# motordriver-v3_1_A3931.net
KiCad netlist of a schematic drawn in Altium Designer
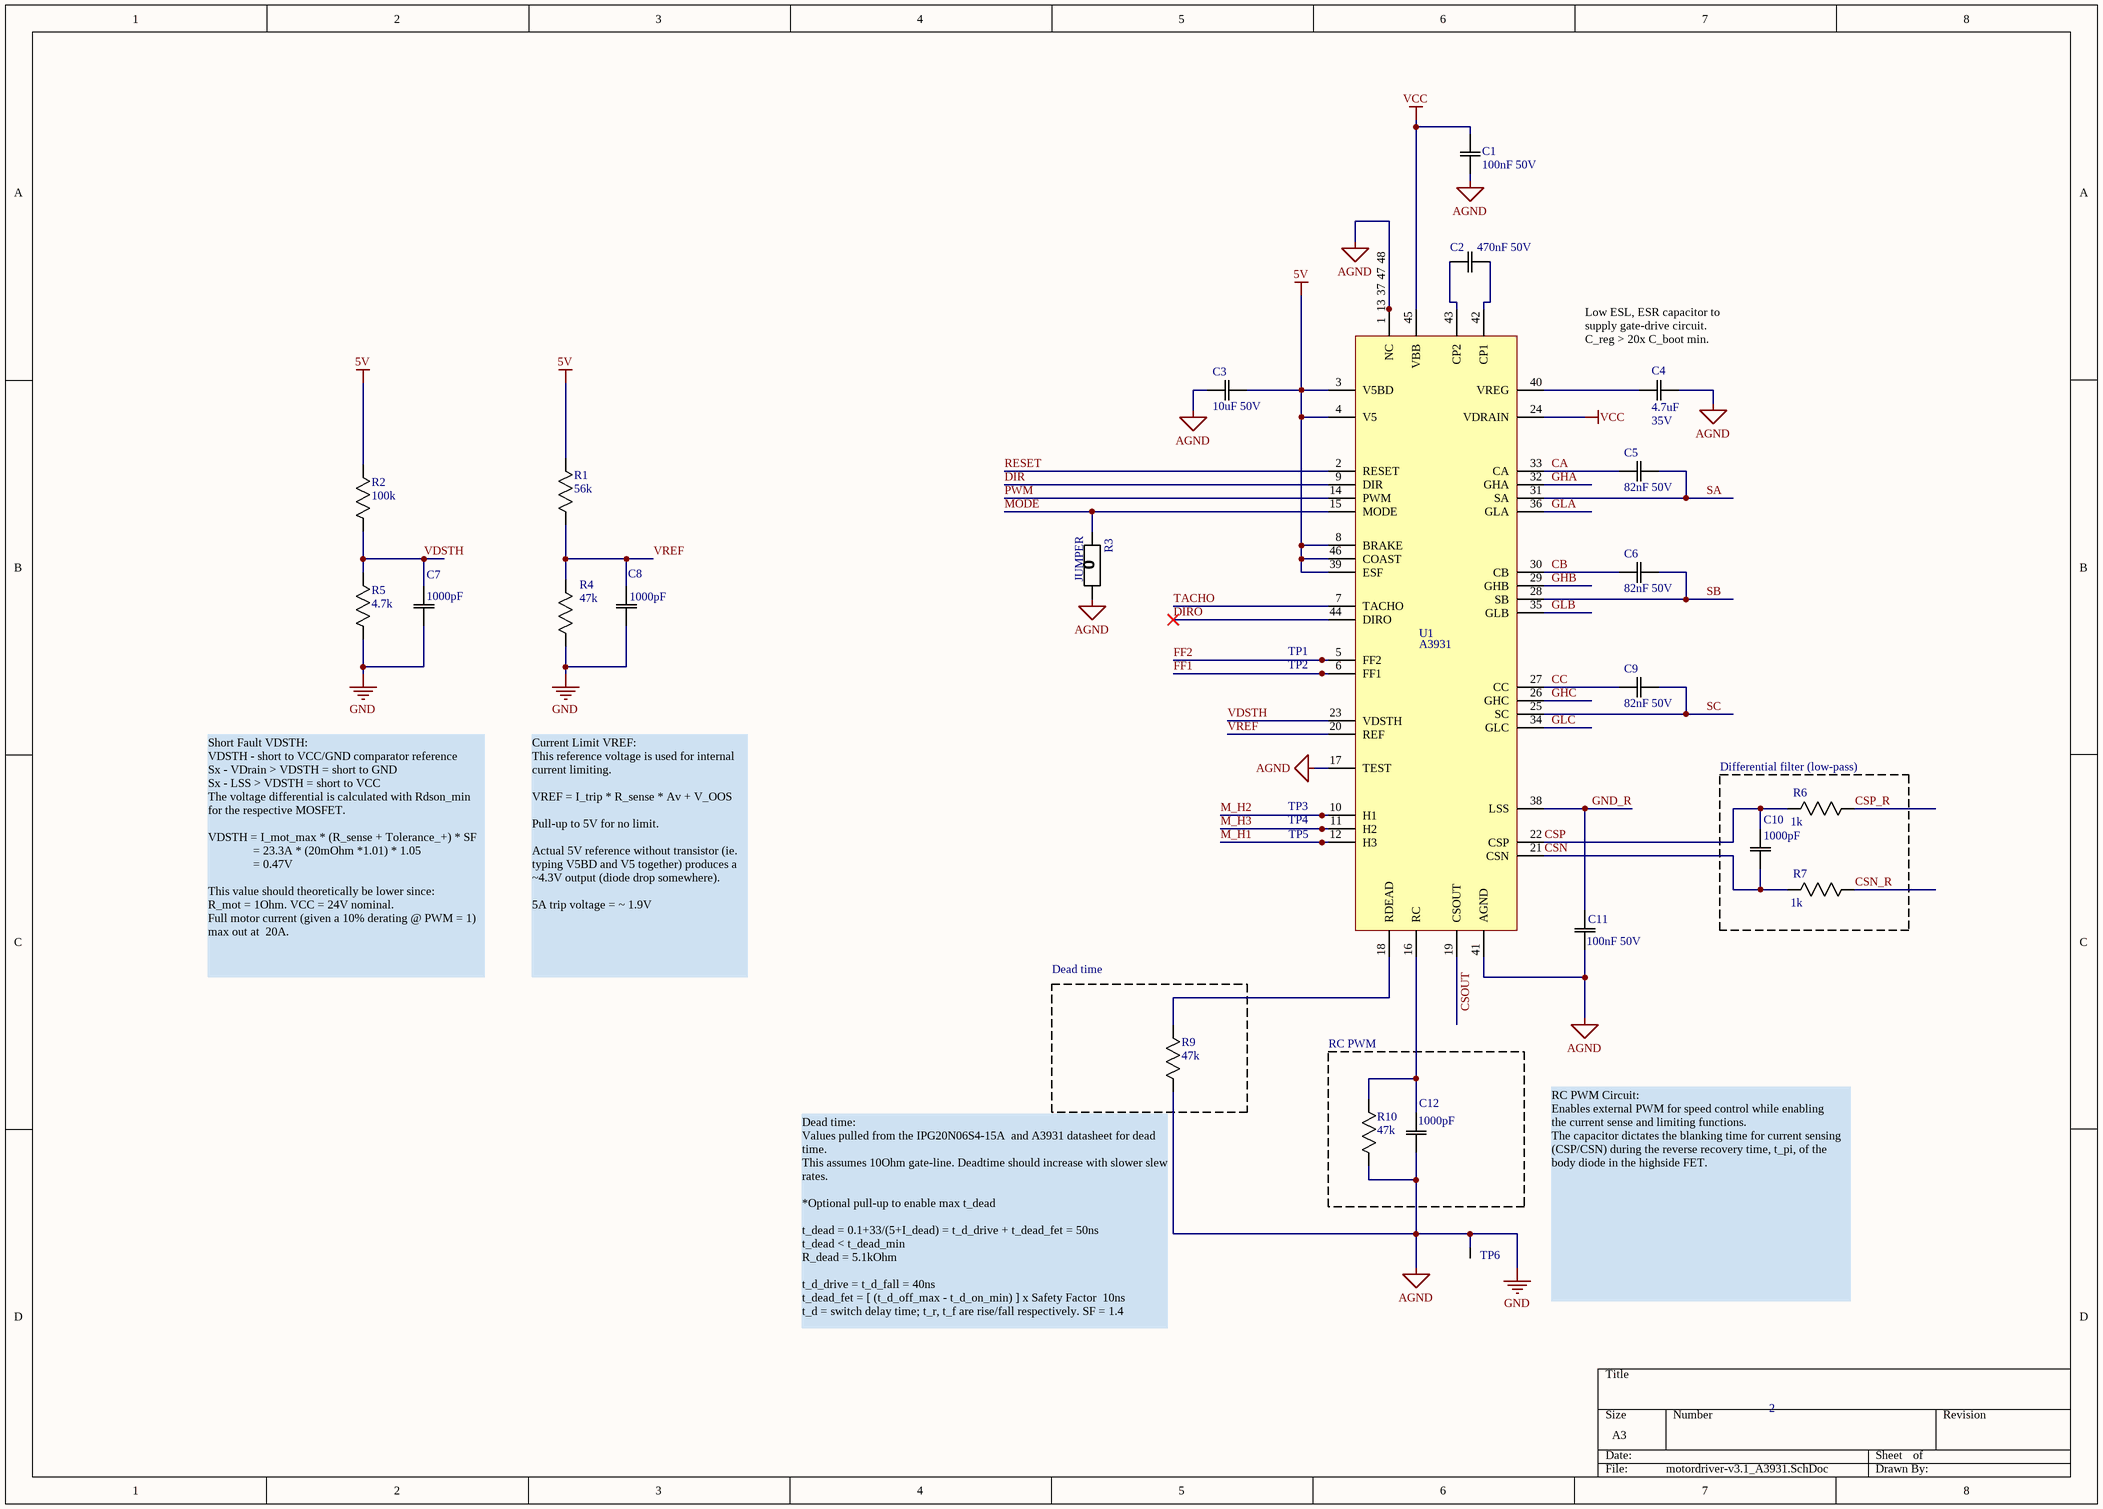
[diagram p0: motordriver-v3.1_A3931.SchDoc]

(export (version "E")
  (design (tool "Eeschema 10.0.6"))
  (components
    (comp (ref "C1")
      (value "100nF 50V")
      (footprint "0603")
      (description "CAP CER 0.1UF 50V X7R 0805")
      (fields (field (name "TOLERANCE") "10%"))
      (libsource (lib "AltiumLibraries") (part "CAP 100nF 50V"))
    )
    (comp (ref "C2")
      (value "470nF 50V")
      (footprint "0603")
      (description "CAP CER 0.1UF 50V X7R 0805")
      (fields (field (name "TOLERANCE") "10%"))
      (libsource (lib "AltiumLibraries") (part "CAP 470nF 50V"))
    )
    (comp (ref "C3")
      (value "10uF 50V")
      (footprint "0805")
      (description "CAP CER 10UF 50V X7R")
      (fields (field (name "TOLERANCE") "10%"))
      (libsource (lib "AltiumLibraries") (part "CAP 10uF 50V"))
    )
    (comp (ref "C4")
      (value "4.7uF")
      (footprint "0603")
      (description "CAP CER 4.7UF 35V X7R 0603/0805")
      (fields (field (name "TOLERANCE") "10%") (field (name "RATING") "35V"))
      (libsource (lib "AltiumLibraries") (part "CAP 4.7uF 35V"))
    )
    (comp (ref "C5")
      (value "82nF 50V")
      (footprint "0603")
      (description "CAP CER 0.082UF 50V X7R 0805")
      (fields (field (name "TOLERANCE") "5%"))
      (libsource (lib "AltiumLibraries") (part "CAP 82nF 50V"))
    )
    (comp (ref "C6")
      (value "82nF 50V")
      (footprint "0603")
      (description "CAP CER 0.082UF 50V X7R 0805")
      (fields (field (name "TOLERANCE") "5%"))
      (libsource (lib "AltiumLibraries") (part "CAP 82nF 50V"))
    )
    (comp (ref "C7")
      (value "1000pF")
      (footprint "0603")
      (description "CAP CER 1000PF 50V X7R 0603/0805")
      (fields (field (name "TOLERANCE") "10%"))
      (libsource (lib "AltiumLibraries") (part "CAP 1000pF 50V"))
    )
    (comp (ref "C8")
      (value "1000pF")
      (footprint "0603")
      (description "CAP CER 1000PF 50V X7R 0603/0805")
      (fields (field (name "TOLERANCE") "10%"))
      (libsource (lib "AltiumLibraries") (part "CAP 1000pF 50V"))
    )
    (comp (ref "C9")
      (value "82nF 50V")
      (footprint "0603")
      (description "CAP CER 0.082UF 50V X7R 0805")
      (fields (field (name "TOLERANCE") "5%"))
      (libsource (lib "AltiumLibraries") (part "CAP 82nF 50V"))
    )
    (comp (ref "C10")
      (value "1000pF")
      (footprint "0603")
      (description "CAP CER 1000PF 50V X7R 0603/0805")
      (fields (field (name "TOLERANCE") "10%"))
      (libsource (lib "AltiumLibraries") (part "CAP 1000pF 50V"))
    )
    (comp (ref "C11")
      (value "100nF 50V")
      (footprint "0603")
      (description "CAP CER 0.1UF 50V X7R 0805")
      (fields (field (name "TOLERANCE") "10%"))
      (libsource (lib "AltiumLibraries") (part "CAP 100nF 50V"))
    )
    (comp (ref "C12")
      (value "1000pF")
      (footprint "0603")
      (description "CAP CER 1000PF 50V X7R 0603/0805")
      (fields (field (name "TOLERANCE") "10%"))
      (libsource (lib "AltiumLibraries") (part "CAP 1000pF 50V"))
    )
    (comp (ref "R1")
      (value "56k")
      (footprint "0603")
      (description "RES SMD 100K OHM 1% 1/8W 0805")
      (fields (field (name "TOLERANCE") "1%"))
      (libsource (lib "") (part "RES 100k 1/8W - 1%_1"))
    )
    (comp (ref "R2")
      (value "100k")
      (footprint "0603")
      (description "RES SMD 100K OHM 1% 1/8W 0805")
      (fields (field (name "TOLERANCE") "1%"))
      (libsource (lib "AltiumLibraries") (part "RES 100k 1/8W - 1%"))
    )
    (comp (ref "R3")
      (value "JUMPER")
      (footprint "0603")
      (description "RES SMD 0 OHM JUMPER GENERIC 0805")
      (libsource (lib "AltiumLibraries") (part "RES 0 JUMPER"))
    )
    (comp (ref "R4")
      (value "47k")
      (footprint "0603")
      (description "RES SMD 47K OHM 1% 1/8W 0805")
      (fields (field (name "TOLERANCE") "1%"))
      (libsource (lib "") (part "RES 47k 1/8W - 1%_1"))
    )
    (comp (ref "R5")
      (value "4.7k")
      (footprint "0603")
      (description "RES SMD 4.7k OHM 1% 1/8W 0805")
      (fields (field (name "TOLERANCE") "1%"))
      (libsource (lib "AltiumLibraries") (part "RES 4.7k 1/8W - 1%"))
    )
    (comp (ref "R6")
      (value "1k")
      (footprint "0603")
      (description "RES SMD 1K OHM 5% 1/8W 0805")
      (fields (field (name "TOLERANCE") "5%"))
      (libsource (lib "AltiumLibraries") (part "RES 1k 1/8W"))
    )
    (comp (ref "R7")
      (value "1k")
      (footprint "0603")
      (description "RES SMD 1K OHM 5% 1/8W 0805")
      (fields (field (name "TOLERANCE") "5%"))
      (libsource (lib "AltiumLibraries") (part "RES 1k 1/8W"))
    )
    (comp (ref "R9")
      (value "47k")
      (footprint "0603")
      (description "RES SMD 5.1K OHM 1% 1/8W 0805")
      (fields (field (name "TOLERANCE") "1%"))
      (libsource (lib "AltiumLibraries") (part "RES 5.1k 1/8W - 1%"))
    )
    (comp (ref "R10")
      (value "47k")
      (footprint "0603")
      (description "RES SMD 47K OHM 1% 1/8W 0805")
      (fields (field (name "TOLERANCE") "1%"))
      (libsource (lib "AltiumLibraries") (part "RES 47k 1/8W - 1%"))
    )
    (comp (ref "TP1")
      (value "Test Point (Via)")
      (footprint "TP")
      (libsource (lib "AltiumLibraries") (part "Test Point (Via)"))
    )
    (comp (ref "TP2")
      (value "Test Point (Via)")
      (footprint "TP")
      (libsource (lib "AltiumLibraries") (part "Test Point (Via)"))
    )
    (comp (ref "TP3")
      (value "Test Point (Via)")
      (footprint "TP")
      (libsource (lib "AltiumLibraries") (part "Test Point (Via)"))
    )
    (comp (ref "TP4")
      (value "Test Point (Via)")
      (footprint "TP")
      (libsource (lib "AltiumLibraries") (part "Test Point (Via)"))
    )
    (comp (ref "TP5")
      (value "Test Point (Via)")
      (footprint "TP")
      (libsource (lib "AltiumLibraries") (part "Test Point (Via)"))
    )
    (comp (ref "TP6")
      (value "Test Point (Via)")
      (footprint "TP")
      (libsource (lib "AltiumLibraries") (part "Test Point (Via)"))
    )
    (comp (ref "U1")
      (value "A3931")
      (footprint "48-LQFP-EP (7x7)")
      (description "IC MOTOR DRIVER 5.5V-50V 48LQFP - Alternative Symbol")
      (libsource (lib "AltiumLibraries") (part "A3931_A1"))
    )
  )
  (nets
    (net (code "1") (name "/CA") (class "Default")
      (node (ref "C5") (pin "1") (pinfunction "C1_1") (pintype "passive"))
      (node (ref "U1") (pin "33") (pinfunction "CA_33") (pintype "passive"))
    )
    (net (code "2") (name "/CB") (class "Default")
      (node (ref "C6") (pin "1") (pinfunction "C1_1") (pintype "passive"))
      (node (ref "U1") (pin "30") (pinfunction "CB_30") (pintype "passive"))
    )
    (net (code "3") (name "/CC") (class "Default")
      (node (ref "C9") (pin "1") (pinfunction "C1_1") (pintype "passive"))
      (node (ref "U1") (pin "27") (pinfunction "CC_27") (pintype "passive"))
    )
    (net (code "4") (name "/CSN") (class "Default")
      (node (ref "C10") (pin "1") (pinfunction "C1_1") (pintype "passive"))
      (node (ref "R7") (pin "2") (pinfunction "R2_2") (pintype "passive"))
      (node (ref "U1") (pin "21") (pinfunction "CSN_21") (pintype "passive"))
    )
    (net (code "5") (name "/CSN_R") (class "Default")
      (node (ref "R7") (pin "1") (pinfunction "R1_1") (pintype "passive"))
    )
    (net (code "6") (name "/CSOUT") (class "Default")
      (node (ref "U1") (pin "19") (pinfunction "CSOUT_19") (pintype "passive"))
    )
    (net (code "7") (name "/CSP") (class "Default")
      (node (ref "C10") (pin "2") (pinfunction "C2_2") (pintype "passive"))
      (node (ref "R6") (pin "2") (pinfunction "R2_2") (pintype "passive"))
      (node (ref "U1") (pin "22") (pinfunction "CSP_22") (pintype "passive"))
    )
    (net (code "8") (name "/CSP_R") (class "Default")
      (node (ref "R6") (pin "1") (pinfunction "R1_1") (pintype "passive"))
    )
    (net (code "9") (name "/DIR") (class "Default")
      (node (ref "U1") (pin "9") (pinfunction "DIR_9") (pintype "passive"))
    )
    (net (code "10") (name "/DIRO") (class "Default")
      (node (ref "U1") (pin "44") (pinfunction "DIRO_44") (pintype "passive+no_connect"))
    )
    (net (code "11") (name "/FF1") (class "Default")
      (node (ref "TP2") (pin "1") (pinfunction "1_1") (pintype "passive"))
      (node (ref "U1") (pin "6") (pinfunction "FF1_6") (pintype "passive"))
    )
    (net (code "12") (name "/FF2") (class "Default")
      (node (ref "TP1") (pin "1") (pinfunction "1_1") (pintype "passive"))
      (node (ref "U1") (pin "5") (pinfunction "FF2_5") (pintype "passive"))
    )
    (net (code "13") (name "/GHA") (class "Default")
      (node (ref "U1") (pin "32") (pinfunction "GHA_32") (pintype "passive"))
    )
    (net (code "14") (name "/GHB") (class "Default")
      (node (ref "U1") (pin "29") (pinfunction "GHB_29") (pintype "passive"))
    )
    (net (code "15") (name "/GHC") (class "Default")
      (node (ref "U1") (pin "26") (pinfunction "GHC_26") (pintype "passive"))
    )
    (net (code "16") (name "/GLA") (class "Default")
      (node (ref "U1") (pin "36") (pinfunction "GLA_36") (pintype "passive"))
    )
    (net (code "17") (name "/GLB") (class "Default")
      (node (ref "U1") (pin "35") (pinfunction "GLB_35") (pintype "passive"))
    )
    (net (code "18") (name "/GLC") (class "Default")
      (node (ref "U1") (pin "34") (pinfunction "GLC_34") (pintype "passive"))
    )
    (net (code "19") (name "/GND_R") (class "Default")
      (node (ref "C11") (pin "2") (pinfunction "C2_2") (pintype "passive"))
      (node (ref "U1") (pin "38") (pinfunction "LSS_38") (pintype "passive"))
    )
    (net (code "20") (name "/MODE") (class "Default")
      (node (ref "R3") (pin "2") (pinfunction "R2_2") (pintype "passive"))
      (node (ref "U1") (pin "15") (pinfunction "MODE_15") (pintype "passive"))
    )
    (net (code "21") (name "/M_H1") (class "Default")
      (node (ref "TP5") (pin "1") (pinfunction "1_1") (pintype "passive"))
      (node (ref "U1") (pin "12") (pinfunction "H3_12") (pintype "passive"))
    )
    (net (code "22") (name "/M_H2") (class "Default")
      (node (ref "TP3") (pin "1") (pinfunction "1_1") (pintype "passive"))
      (node (ref "U1") (pin "10") (pinfunction "H1_10") (pintype "passive"))
    )
    (net (code "23") (name "/M_H3") (class "Default")
      (node (ref "TP4") (pin "1") (pinfunction "1_1") (pintype "passive"))
      (node (ref "U1") (pin "11") (pinfunction "H2_11") (pintype "passive"))
    )
    (net (code "24") (name "/PWM") (class "Default")
      (node (ref "U1") (pin "14") (pinfunction "PWM_14") (pintype "passive"))
    )
    (net (code "25") (name "/RESET") (class "Default")
      (node (ref "U1") (pin "2") (pinfunction "RESET_2") (pintype "passive"))
    )
    (net (code "26") (name "/SA") (class "Default")
      (node (ref "C5") (pin "2") (pinfunction "C2_2") (pintype "passive"))
      (node (ref "U1") (pin "31") (pinfunction "SA_31") (pintype "passive"))
    )
    (net (code "27") (name "/SB") (class "Default")
      (node (ref "C6") (pin "2") (pinfunction "C2_2") (pintype "passive"))
      (node (ref "U1") (pin "28") (pinfunction "SB_28") (pintype "passive"))
    )
    (net (code "28") (name "/SC") (class "Default")
      (node (ref "C9") (pin "2") (pinfunction "C2_2") (pintype "passive"))
      (node (ref "U1") (pin "25") (pinfunction "SC_25") (pintype "passive"))
    )
    (net (code "29") (name "/TACHO") (class "Default")
      (node (ref "U1") (pin "7") (pinfunction "TACHO_7") (pintype "passive"))
    )
    (net (code "30") (name "/VDSTH") (class "Default")
      (node (ref "C7") (pin "2") (pinfunction "C2_2") (pintype "passive"))
      (node (ref "R2") (pin "2") (pinfunction "R2_2") (pintype "passive"))
      (node (ref "R5") (pin "1") (pinfunction "R1_1") (pintype "passive"))
      (node (ref "U1") (pin "23") (pinfunction "VDSTH_23") (pintype "passive"))
    )
    (net (code "31") (name "/VREF") (class "Default")
      (node (ref "C8") (pin "2") (pinfunction "C2_2") (pintype "passive"))
      (node (ref "R1") (pin "2") (pinfunction "R2_2") (pintype "passive"))
      (node (ref "R4") (pin "2") (pinfunction "R2_2") (pintype "passive"))
      (node (ref "U1") (pin "20") (pinfunction "REF_20") (pintype "passive"))
    )
    (net (code "32") (name "5V") (class "Default")
      (node (ref "C3") (pin "2") (pinfunction "C2_2") (pintype "passive"))
      (node (ref "R1") (pin "1") (pinfunction "R1_1") (pintype "passive"))
      (node (ref "R2") (pin "1") (pinfunction "R1_1") (pintype "passive"))
      (node (ref "U1") (pin "3") (pinfunction "V5BD_3") (pintype "passive"))
      (node (ref "U1") (pin "39") (pinfunction "ESF_39") (pintype "passive"))
      (node (ref "U1") (pin "4") (pinfunction "V5_4") (pintype "passive"))
      (node (ref "U1") (pin "46") (pinfunction "COAST_46") (pintype "passive"))
      (node (ref "U1") (pin "8") (pinfunction "BRAKE_8") (pintype "passive"))
    )
    (net (code "33") (name "AGND") (class "Default")
      (node (ref "C1") (pin "1") (pinfunction "C1_1") (pintype "passive"))
      (node (ref "C11") (pin "1") (pinfunction "C1_1") (pintype "passive"))
      (node (ref "C12") (pin "1") (pinfunction "C1_1") (pintype "passive"))
      (node (ref "C3") (pin "1") (pinfunction "C1_1") (pintype "passive"))
      (node (ref "C4") (pin "2") (pinfunction "C2_2") (pintype "passive"))
      (node (ref "C7") (pin "1") (pinfunction "C1_1") (pintype "passive"))
      (node (ref "C8") (pin "1") (pinfunction "C1_1") (pintype "passive"))
      (node (ref "R10") (pin "2") (pinfunction "R2_2") (pintype "passive"))
      (node (ref "R3") (pin "1") (pinfunction "R1_1") (pintype "passive"))
      (node (ref "R4") (pin "1") (pinfunction "R1_1") (pintype "passive"))
      (node (ref "R5") (pin "2") (pinfunction "R2_2") (pintype "passive"))
      (node (ref "R9") (pin "2") (pinfunction "R2_2") (pintype "passive"))
      (node (ref "TP6") (pin "1") (pinfunction "1_1") (pintype "passive"))
      (node (ref "U1") (pin "1") (pinfunction "NC_1") (pintype "passive"))
      (node (ref "U1") (pin "13") (pinfunction "13_13") (pintype "passive"))
      (node (ref "U1") (pin "17") (pinfunction "TEST_17") (pintype "passive"))
      (node (ref "U1") (pin "37") (pinfunction "NC_37") (pintype "passive"))
      (node (ref "U1") (pin "41") (pinfunction "AGND_41") (pintype "passive"))
      (node (ref "U1") (pin "47") (pinfunction "NC_47") (pintype "passive"))
      (node (ref "U1") (pin "48") (pinfunction "NC_48") (pintype "passive"))
    )
    (net (code "34") (name "Net-(C2-C1)") (class "Default")
      (node (ref "C2") (pin "1") (pinfunction "C1_1") (pintype "passive"))
      (node (ref "U1") (pin "43") (pinfunction "CP2_43") (pintype "passive"))
    )
    (net (code "35") (name "Net-(C2-C2)") (class "Default")
      (node (ref "C2") (pin "2") (pinfunction "C2_2") (pintype "passive"))
      (node (ref "U1") (pin "42") (pinfunction "CP1_42") (pintype "passive"))
    )
    (net (code "36") (name "Net-(C4-C1)") (class "Default")
      (node (ref "C4") (pin "1") (pinfunction "C1_1") (pintype "passive"))
      (node (ref "U1") (pin "40") (pinfunction "VREG_40") (pintype "passive"))
    )
    (net (code "37") (name "Net-(C12-C2)") (class "Default")
      (node (ref "C12") (pin "2") (pinfunction "C2_2") (pintype "passive"))
      (node (ref "R10") (pin "1") (pinfunction "R1_1") (pintype "passive"))
      (node (ref "U1") (pin "16") (pinfunction "RC_16") (pintype "passive"))
    )
    (net (code "38") (name "Net-(R9-R1)") (class "Default")
      (node (ref "R9") (pin "1") (pinfunction "R1_1") (pintype "passive"))
      (node (ref "U1") (pin "18") (pinfunction "RDEAD_18") (pintype "passive"))
    )
    (net (code "39") (name "VCC") (class "Default")
      (node (ref "C1") (pin "2") (pinfunction "C2_2") (pintype "passive"))
      (node (ref "U1") (pin "24") (pinfunction "VDRAIN_24") (pintype "passive"))
      (node (ref "U1") (pin "45") (pinfunction "VBB_45") (pintype "passive"))
    )
  )
)
